# 23Kxxx.net
KiCad netlist of a schematic drawn in EAGLE
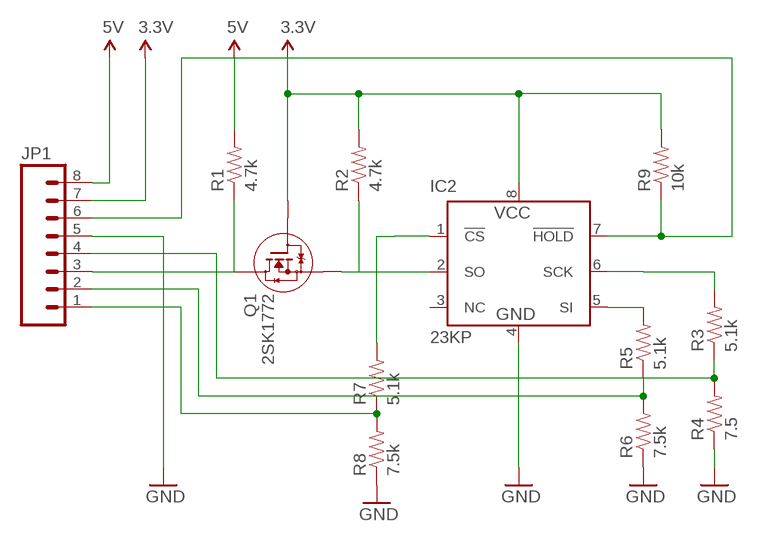
[diagram p0: schematic, sheet 1]

(export (version "E")
  (design (tool "Eeschema 10.0.6"))
  (components
    (comp (ref "IC2")
      (value "23KP")
      (footprint "eagle-import:DIL8")
      (libsource (lib "eagle-import") (part "23KP"))
    )
    (comp (ref "JP1")
      (value "M081X08")
      (footprint "eagle-import:1X08")
      (libsource (lib "eagle-import") (part "M081X08"))
    )
    (comp (ref "Q1")
      (value "2SK1772")
      (footprint "eagle-import:SOT89")
      (libsource (lib "eagle-import") (part "2SK1772"))
    )
    (comp (ref "R1")
      (value "4.7k")
      (footprint "eagle-import:AXIAL-0.3")
      (libsource (lib "eagle-import") (part "RESISTORAXIAL-0.3"))
    )
    (comp (ref "R2")
      (value "4.7k")
      (footprint "eagle-import:AXIAL-0.3")
      (libsource (lib "eagle-import") (part "RESISTORAXIAL-0.3"))
    )
    (comp (ref "R3")
      (value "5.1k")
      (footprint "eagle-import:AXIAL-0.3")
      (libsource (lib "eagle-import") (part "RESISTORAXIAL-0.3"))
    )
    (comp (ref "R4")
      (value "7.5")
      (footprint "eagle-import:AXIAL-0.3")
      (libsource (lib "eagle-import") (part "RESISTORAXIAL-0.3"))
    )
    (comp (ref "R5")
      (value "5.1k")
      (footprint "eagle-import:AXIAL-0.3")
      (libsource (lib "eagle-import") (part "RESISTORAXIAL-0.3"))
    )
    (comp (ref "R6")
      (value "7.5k")
      (footprint "eagle-import:AXIAL-0.3")
      (libsource (lib "eagle-import") (part "RESISTORAXIAL-0.3"))
    )
    (comp (ref "R7")
      (value "5.1k")
      (footprint "eagle-import:AXIAL-0.3")
      (libsource (lib "eagle-import") (part "RESISTORAXIAL-0.3"))
    )
    (comp (ref "R8")
      (value "7.5k")
      (footprint "eagle-import:AXIAL-0.3")
      (libsource (lib "eagle-import") (part "RESISTORAXIAL-0.3"))
    )
    (comp (ref "R9")
      (value "10k")
      (footprint "eagle-import:AXIAL-0.3")
      (libsource (lib "eagle-import") (part "RESISTORAXIAL-0.3"))
    )
  )
  (nets
    (net (code "1") (name "3.3V") (class "Default")
      (node (ref "IC2") (pin "8") (pinfunction "VCC_8") (pintype "power_in"))
      (node (ref "JP1") (pin "7") (pinfunction "7_7") (pintype "passive"))
      (node (ref "Q1") (pin "1") (pinfunction "G_1") (pintype "passive"))
      (node (ref "R2") (pin "P$2") (pinfunction "2_P$2") (pintype "passive"))
      (node (ref "R9") (pin "P$2") (pinfunction "2_P$2") (pintype "passive"))
    )
    (net (code "2") (name "5V") (class "Default")
      (node (ref "JP1") (pin "8") (pinfunction "8_8") (pintype "passive"))
      (node (ref "R1") (pin "P$2") (pinfunction "2_P$2") (pintype "passive"))
    )
    (net (code "3") (name "GND") (class "Default")
      (node (ref "IC2") (pin "4") (pinfunction "GND_4") (pintype "power_in"))
      (node (ref "JP1") (pin "5") (pinfunction "5_5") (pintype "passive"))
      (node (ref "R4") (pin "P$1") (pinfunction "1_P$1") (pintype "passive"))
      (node (ref "R6") (pin "P$1") (pinfunction "1_P$1") (pintype "passive"))
      (node (ref "R8") (pin "P$1") (pinfunction "1_P$1") (pintype "passive"))
    )
    (net (code "4") (name "Net-(IC2-SCK)") (class "Default")
      (node (ref "IC2") (pin "6") (pinfunction "SCK_6") (pintype "input"))
      (node (ref "R3") (pin "P$2") (pinfunction "2_P$2") (pintype "passive"))
    )
    (net (code "5") (name "Net-(IC2-SI)") (class "Default")
      (node (ref "IC2") (pin "5") (pinfunction "SI_5") (pintype "input"))
      (node (ref "R5") (pin "P$2") (pinfunction "2_P$2") (pintype "passive"))
    )
    (net (code "6") (name "Net-(IC2-SO)") (class "Default")
      (node (ref "IC2") (pin "2") (pinfunction "SO_2") (pintype "bidirectional"))
      (node (ref "Q1") (pin "3") (pinfunction "S_3") (pintype "passive"))
      (node (ref "R2") (pin "P$1") (pinfunction "1_P$1") (pintype "passive"))
    )
    (net (code "7") (name "Net-(IC2-~{CS})") (class "Default")
      (node (ref "IC2") (pin "1") (pinfunction "~{CS}_1") (pintype "input"))
      (node (ref "R7") (pin "P$2") (pinfunction "2_P$2") (pintype "passive"))
    )
    (net (code "8") (name "Net-(IC2-~{HOLD})") (class "Default")
      (node (ref "IC2") (pin "7") (pinfunction "~{HOLD}_7") (pintype "input"))
      (node (ref "JP1") (pin "6") (pinfunction "6_6") (pintype "passive"))
      (node (ref "R9") (pin "P$1") (pinfunction "1_P$1") (pintype "passive"))
    )
    (net (code "9") (name "Net-(R1-1)") (class "Default")
      (node (ref "JP1") (pin "3") (pinfunction "3_3") (pintype "passive"))
      (node (ref "Q1") (pin "2") (pinfunction "D_2") (pintype "passive"))
      (node (ref "Q1") (pin "2@1") (pinfunction "D_2@1") (pintype "passive"))
      (node (ref "R1") (pin "P$1") (pinfunction "1_P$1") (pintype "passive"))
    )
    (net (code "10") (name "Net-(R3-1)") (class "Default")
      (node (ref "JP1") (pin "4") (pinfunction "4_4") (pintype "passive"))
      (node (ref "R3") (pin "P$1") (pinfunction "1_P$1") (pintype "passive"))
      (node (ref "R4") (pin "P$2") (pinfunction "2_P$2") (pintype "passive"))
    )
    (net (code "11") (name "Net-(R5-1)") (class "Default")
      (node (ref "JP1") (pin "2") (pinfunction "2_2") (pintype "passive"))
      (node (ref "R5") (pin "P$1") (pinfunction "1_P$1") (pintype "passive"))
      (node (ref "R6") (pin "P$2") (pinfunction "2_P$2") (pintype "passive"))
    )
    (net (code "12") (name "Net-(R7-1)") (class "Default")
      (node (ref "JP1") (pin "1") (pinfunction "1_1") (pintype "passive"))
      (node (ref "R7") (pin "P$1") (pinfunction "1_P$1") (pintype "passive"))
      (node (ref "R8") (pin "P$2") (pinfunction "2_P$2") (pintype "passive"))
    )
    (net (code "13") (name "unconnected-(IC2-NC-Pad3)") (class "Default")
      (node (ref "IC2") (pin "3") (pinfunction "NC_3") (pintype "no_connect"))
    )
  )
)
